# 8_-_DAC_and_MIC.net
KiCad netlist of a schematic drawn in Altium Designer
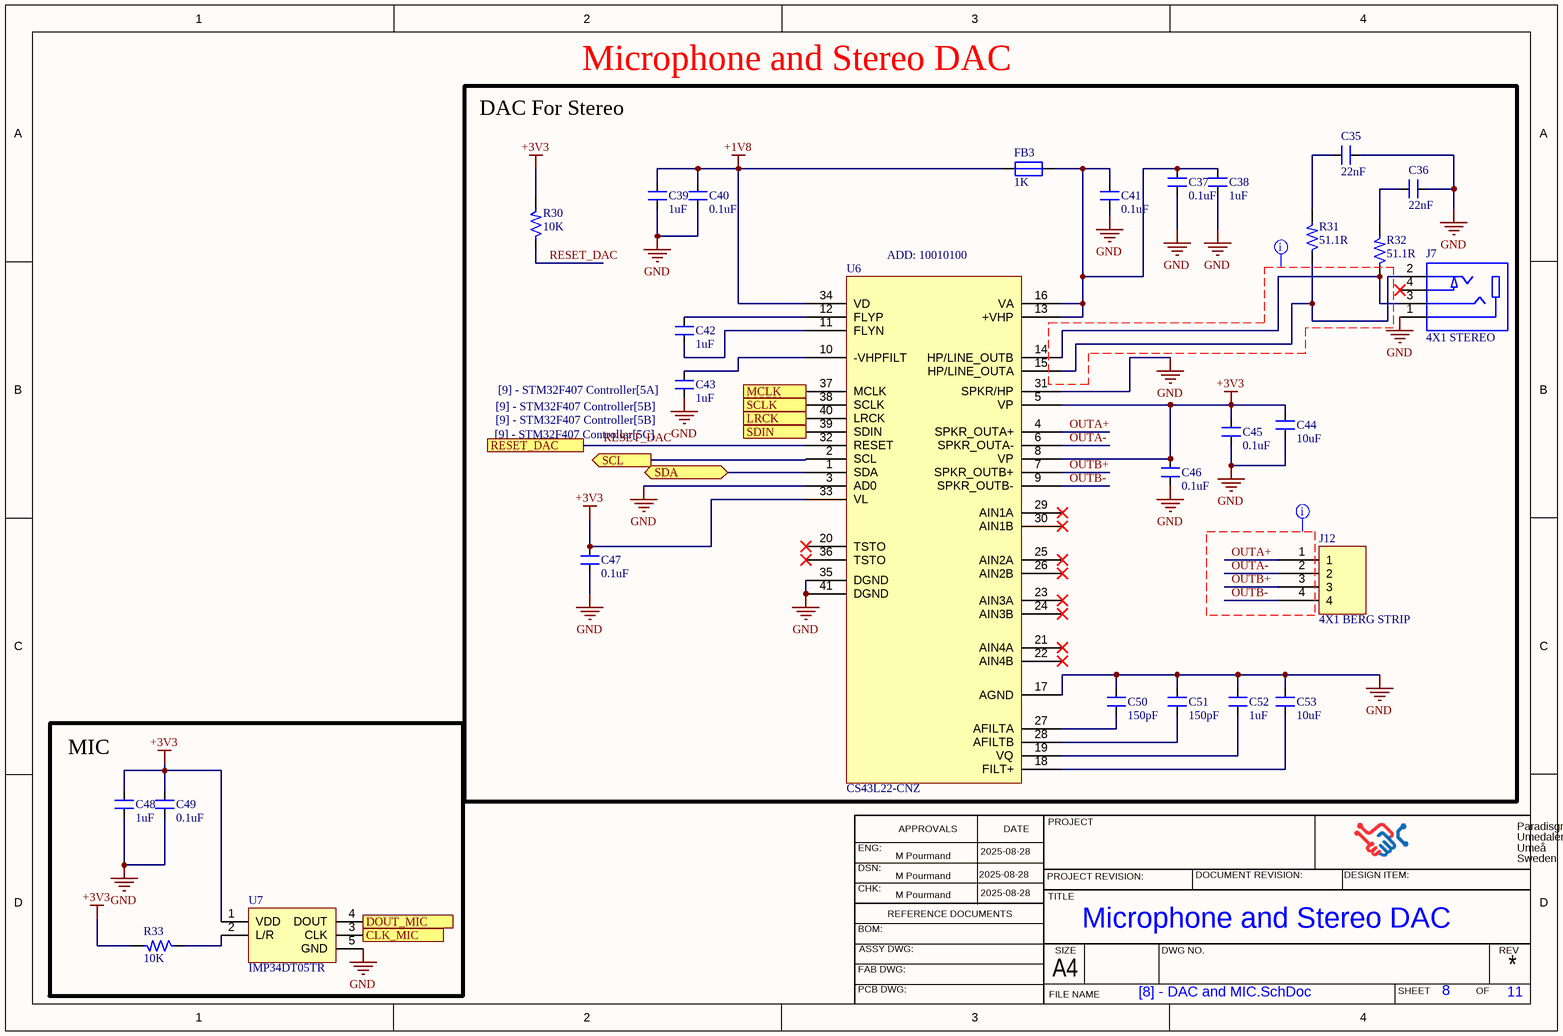
[diagram p0: [8] - DAC and MIC.SchDoc]

(export (version "E")
  (design (tool "Eeschema 10.0.6"))
  (components
    (comp (ref "C35")
      (value "22nF")
      (footprint "CAP_0805")
      (description "0.022µF ±10% 50V Ceramic Capacitor X7R 0805 (2012 Metric)")
      (fields
        (field (name "MANUFACTURER") "Samsung Electro-Mechanics")
        (field (name "MANUFACTURER PART NUMBER") "CL21B223KBANNNC")
      )
      (libsource (lib "ESTEEMPCBLIB") (part "CAP_22nF-50V-10%-0805"))
    )
    (comp (ref "C36")
      (value "22nF")
      (footprint "CAP_0805")
      (description "0.022µF ±10% 50V Ceramic Capacitor X7R 0805 (2012 Metric)")
      (fields
        (field (name "MANUFACTURER") "Samsung Electro-Mechanics")
        (field (name "MANUFACTURER PART NUMBER") "CL21B223KBANNNC")
      )
      (libsource (lib "ESTEEMPCBLIB") (part "CAP_22nF-50V-10%-0805"))
    )
    (comp (ref "C37")
      (value "0.1uF")
      (footprint "CAP_0805")
      (description "0.1µF ±5% 50V Ceramic Capacitor X7R 0805 (2012 Metric)")
      (fields
        (field (name "MANUFACTURER") "AVX Corporation")
        (field (name "MANUFACTURER PART NUMBER") "08055C104JAT4A")
      )
      (libsource (lib "ESTEEMPCBLIB") (part "CAP_0.1uF-50V-5%-0805"))
    )
    (comp (ref "C38")
      (value "1uF")
      (footprint "CAP_0805")
      (description "1µF ±5% 50V Ceramic Capacitor X7R 0805 (2012 Metric)")
      (fields
        (field (name "MANUFACTURER") "Samsung")
        (field (name "MANUFACTURER PART NUMBER") "CC0805JKX7R9BB105")
      )
      (libsource (lib "ESTEEMPCBLIB") (part "CAP_1uF-50V-5%-0805"))
    )
    (comp (ref "C39")
      (value "1uF")
      (footprint "CAP_0805")
      (description "1µF ±5% 50V Ceramic Capacitor X7R 0805 (2012 Metric)")
      (fields
        (field (name "MANUFACTURER") "Samsung")
        (field (name "MANUFACTURER PART NUMBER") "CC0805JKX7R9BB105")
      )
      (libsource (lib "ESTEEMPCBLIB") (part "CAP_1uF-50V-5%-0805"))
    )
    (comp (ref "C40")
      (value "0.1uF")
      (footprint "CAP_0805")
      (description "0.1µF ±5% 50V Ceramic Capacitor X7R 0805 (2012 Metric)")
      (fields
        (field (name "MANUFACTURER") "AVX Corporation")
        (field (name "MANUFACTURER PART NUMBER") "08055C104JAT4A")
      )
      (libsource (lib "ESTEEMPCBLIB") (part "CAP_0.1uF-50V-5%-0805"))
    )
    (comp (ref "C41")
      (value "0.1uF")
      (footprint "CAP_0805")
      (description "0.1µF ±5% 50V Ceramic Capacitor X7R 0805 (2012 Metric)")
      (fields
        (field (name "MANUFACTURER") "AVX Corporation")
        (field (name "MANUFACTURER PART NUMBER") "08055C104JAT4A")
      )
      (libsource (lib "ESTEEMPCBLIB") (part "CAP_0.1uF-50V-5%-0805"))
    )
    (comp (ref "C42")
      (value "1uF")
      (footprint "CAP_0805")
      (description "1µF ±5% 50V Ceramic Capacitor X7R 0805 (2012 Metric)")
      (fields
        (field (name "MANUFACTURER") "Samsung")
        (field (name "MANUFACTURER PART NUMBER") "CC0805JKX7R9BB105")
      )
      (libsource (lib "ESTEEMPCBLIB") (part "CAP_1uF-50V-5%-0805"))
    )
    (comp (ref "C43")
      (value "1uF")
      (footprint "CAP_0805")
      (description "1µF ±5% 50V Ceramic Capacitor X7R 0805 (2012 Metric)")
      (fields
        (field (name "MANUFACTURER") "Samsung")
        (field (name "MANUFACTURER PART NUMBER") "CC0805JKX7R9BB105")
      )
      (libsource (lib "ESTEEMPCBLIB") (part "CAP_1uF-50V-5%-0805"))
    )
    (comp (ref "C44")
      (value "10uF")
      (footprint "CAP_1206")
      (description "10µF ±10% 50V Ceramic Capacitor X7R 1206 (3216 Metric)")
      (fields
        (field (name "MANUFACTURER") "KEMET")
        (field (name "MANUFACTURER PART NUMBER") "CL31B106KBHNNNE")
      )
      (libsource (lib "ESTEEMPCBLIB") (part "CAP_10uF-50V-10%-1206"))
    )
    (comp (ref "C45")
      (value "0.1uF")
      (footprint "CAP_0805")
      (description "0.1µF ±5% 50V Ceramic Capacitor X7R 0805 (2012 Metric)")
      (fields
        (field (name "MANUFACTURER") "AVX Corporation")
        (field (name "MANUFACTURER PART NUMBER") "08055C104JAT4A")
      )
      (libsource (lib "ESTEEMPCBLIB") (part "CAP_0.1uF-50V-5%-0805"))
    )
    (comp (ref "C46")
      (value "0.1uF")
      (footprint "CAP_0805")
      (description "0.1µF ±5% 50V Ceramic Capacitor X7R 0805 (2012 Metric)")
      (fields
        (field (name "MANUFACTURER") "AVX Corporation")
        (field (name "MANUFACTURER PART NUMBER") "08055C104JAT4A")
      )
      (libsource (lib "ESTEEMPCBLIB") (part "CAP_0.1uF-50V-5%-0805"))
    )
    (comp (ref "C47")
      (value "0.1uF")
      (footprint "CAP_0805")
      (description "0.1µF ±5% 50V Ceramic Capacitor X7R 0805 (2012 Metric)")
      (fields
        (field (name "MANUFACTURER") "AVX Corporation")
        (field (name "MANUFACTURER PART NUMBER") "08055C104JAT4A")
      )
      (libsource (lib "ESTEEMPCBLIB") (part "CAP_0.1uF-50V-5%-0805"))
    )
    (comp (ref "C48")
      (value "1uF")
      (footprint "CAP_0805")
      (description "1µF ±5% 50V Ceramic Capacitor X7R 0805 (2012 Metric)")
      (fields
        (field (name "MANUFACTURER") "Samsung")
        (field (name "MANUFACTURER PART NUMBER") "CC0805JKX7R9BB105")
      )
      (libsource (lib "ESTEEMPCBLIB") (part "CAP_1uF-50V-5%-0805"))
    )
    (comp (ref "C49")
      (value "0.1uF")
      (footprint "CAP_0805")
      (description "0.1µF ±5% 50V Ceramic Capacitor X7R 0805 (2012 Metric)")
      (fields
        (field (name "MANUFACTURER") "AVX Corporation")
        (field (name "MANUFACTURER PART NUMBER") "08055C104JAT4A")
      )
      (libsource (lib "ESTEEMPCBLIB") (part "CAP_0.1uF-50V-5%-0805"))
    )
    (comp (ref "C50")
      (value "150pF")
      (footprint "CAP_0805")
      (description "150pF ±10% 50V Ceramic Capacitor C0G, NP0 0805 (2012 Metric)")
      (fields
        (field (name "MANUFACTURER") "AVX Corporation")
        (field (name "MANUFACTURER PART NUMBER") "08055A151KAT2A")
      )
      (libsource (lib "ESTEEMPCBLIB") (part "CAP_150pF-50V-10%-0805"))
    )
    (comp (ref "C51")
      (value "150pF")
      (footprint "CAP_0805")
      (description "150pF ±10% 50V Ceramic Capacitor C0G, NP0 0805 (2012 Metric)")
      (fields
        (field (name "MANUFACTURER") "AVX Corporation")
        (field (name "MANUFACTURER PART NUMBER") "08055A151KAT2A")
      )
      (libsource (lib "ESTEEMPCBLIB") (part "CAP_150pF-50V-10%-0805"))
    )
    (comp (ref "C52")
      (value "1uF")
      (footprint "CAP_0805")
      (description "1µF ±5% 50V Ceramic Capacitor X7R 0805 (2012 Metric)")
      (fields
        (field (name "MANUFACTURER") "Samsung")
        (field (name "MANUFACTURER PART NUMBER") "CC0805JKX7R9BB105")
      )
      (libsource (lib "ESTEEMPCBLIB") (part "CAP_1uF-50V-5%-0805"))
    )
    (comp (ref "C53")
      (value "10uF")
      (footprint "CAP_1206")
      (description "10µF ±10% 50V Ceramic Capacitor X7R 1206 (3216 Metric)")
      (fields
        (field (name "MANUFACTURER") "KEMET")
        (field (name "MANUFACTURER PART NUMBER") "CL31B106KBHNNNE")
      )
      (libsource (lib "ESTEEMPCBLIB") (part "CAP_10uF-50V-10%-1206"))
    )
    (comp (ref "FB3")
      (value "1K")
      (footprint "IND_0805")
      (description "1 kOhms @ 100MHz 1 Power Line Ferrite Bead 0805 (2012 Metric) 1.6A")
      (fields
        (field (name "MANUFACTURER") "Laird")
        (field (name "MANUFACTURER PART NUMBER") "BLM21SP102SH1D")
      )
      (libsource (lib "ESTEEMPCBLIB") (part "FB_1K-100MHZ-1.6A-0805"))
    )
    (comp (ref "J7")
      (value "4X1 STEREO")
      (footprint "CON_SJ-2504A-SMT-TR_SMD")
      (fields
        (field (name "MANUFACTURER") "CUI Devices")
        (field (name "MANUFACTURER PART NUMBER") "SJ-2504A-SMT-TR")
      )
      (libsource (lib "ESTEEMPCBLIB") (part "CON-PLG-STEREO_4X1-100-RA-SMD"))
    )
    (comp (ref "J12")
      (value "4X1 BERG STRIP")
      (footprint "CON4_100_40D72_TH_ST_MALE")
      (description "4 Pins, 1 Row 2.54mm Pitch, Straight bergstrip, Male")
      (fields (field (name "MANUFACTURER") "NA"))
      (libsource (lib "ESTEEMPCBLIB") (part "CON-BS-PLG_4X1-100-ST-TH"))
    )
    (comp (ref "R30")
      (value "10K")
      (footprint "RES_0603")
      (description "10 kOhms ±1% 0.1W, 1/10W Chip Resistor 0603 (1608 Metric) Automotive AEC-Q200 Thick Film")
      (fields (field (name "MANUFACTURER") "Walsin") (field (name "MANUFACTURER PART NUMBER") "WR06X1002FTL"))
      (libsource (lib "ESTEEMPCBLIB") (part "RES_10K-0.1W-1%-0603"))
    )
    (comp (ref "R31")
      (value "51.1R")
      (footprint "RES_0603")
      (description "51.1 Ohms ±1% 0.1W, 1/10W Chip Resistor 0603 (1608 Metric) Thick Film")
      (fields
        (field (name "MANUFACTURER") "Vishay Dale")
        (field (name "MANUFACTURER PART NUMBER") "CRCW060351R1FKEAC")
      )
      (libsource (lib "ESTEEMPCBLIB") (part "RES_51.1R-0.1W-1%-0603"))
    )
    (comp (ref "R32")
      (value "51.1R")
      (footprint "RES_0603")
      (description "51.1 Ohms ±1% 0.1W, 1/10W Chip Resistor 0603 (1608 Metric) Thick Film")
      (fields
        (field (name "MANUFACTURER") "Vishay Dale")
        (field (name "MANUFACTURER PART NUMBER") "CRCW060351R1FKEAC")
      )
      (libsource (lib "ESTEEMPCBLIB") (part "RES_51.1R-0.1W-1%-0603"))
    )
    (comp (ref "R33")
      (value "10K")
      (footprint "RES_0603")
      (description "10 kOhms ±1% 0.1W, 1/10W Chip Resistor 0603 (1608 Metric) Automotive AEC-Q200 Thick Film")
      (fields (field (name "MANUFACTURER") "Walsin") (field (name "MANUFACTURER PART NUMBER") "WR06X1002FTL"))
      (libsource (lib "ESTEEMPCBLIB") (part "RES_10K-0.1W-1%-0603"))
    )
    (comp (ref "U6")
      (value "CS43L22-CNZ")
      (footprint "QFN40_19_284_33X9_SMD")
      (description "Audio D/A Converter ICs Low Power Stereo DAC w/ClassD Spkr Driver")
      (fields (field (name "MANUFACTURER") "Cirrus Logic"))
      (libsource (lib "ESTEEMPCBLIB") (part "IC_CS43L22"))
    )
    (comp (ref "U7")
      (value "IMP34DT05TR")
      (footprint "HCLGA-4_53_137_15X37_SMD")
      (description "MEMS Microphones AUTO & INDUSTRIAL SENSORS")
      (fields (field (name "MANUFACTURER") "STMicroelectronics"))
      (libsource (lib "ESTEEMPCBLIB") (part "IC_IMP34DT05TR"))
    )
  )
  (nets
    (net (code "1") (name "+1V8") (class "Default")
      (node (ref "C39") (pin "2") (pinfunction "2_2") (pintype "passive"))
      (node (ref "C40") (pin "2") (pinfunction "2_2") (pintype "passive"))
      (node (ref "FB3") (pin "1") (pinfunction "1_1") (pintype "passive"))
      (node (ref "U6") (pin "34") (pinfunction "VD_34") (pintype "passive"))
    )
    (net (code "2") (name "+3V3") (class "Default")
      (node (ref "C44") (pin "1") (pinfunction "1_1") (pintype "passive"))
      (node (ref "C45") (pin "2") (pinfunction "2_2") (pintype "passive"))
      (node (ref "C46") (pin "2") (pinfunction "2_2") (pintype "passive"))
      (node (ref "C47") (pin "2") (pinfunction "2_2") (pintype "passive"))
      (node (ref "C48") (pin "2") (pinfunction "2_2") (pintype "passive"))
      (node (ref "C49") (pin "2") (pinfunction "2_2") (pintype "passive"))
      (node (ref "R30") (pin "2") (pinfunction "2_2") (pintype "passive"))
      (node (ref "R33") (pin "2") (pinfunction "2_2") (pintype "passive"))
      (node (ref "U6") (pin "33") (pinfunction "VL_33") (pintype "passive"))
      (node (ref "U6") (pin "5") (pinfunction "VP_5") (pintype "passive"))
      (node (ref "U6") (pin "8") (pinfunction "VP_8") (pintype "passive"))
      (node (ref "U7") (pin "1") (pinfunction "VDD_1") (pintype "passive"))
    )
    (net (code "3") (name "/CLK_MIC") (class "Default")
      (node (ref "U7") (pin "3") (pinfunction "CLK_3") (pintype "passive"))
    )
    (net (code "4") (name "/DOUT_MIC") (class "Default")
      (node (ref "U7") (pin "4") (pinfunction "DOUT_4") (pintype "passive"))
    )
    (net (code "5") (name "/LRCK") (class "Default")
      (node (ref "U6") (pin "40") (pinfunction "LRCK_40") (pintype "passive"))
    )
    (net (code "6") (name "/MCLK") (class "Default")
      (node (ref "U6") (pin "37") (pinfunction "MCLK_37") (pintype "passive"))
    )
    (net (code "7") (name "/OUTA+") (class "Default")
      (node (ref "J12") (pin "1") (pinfunction "1_1") (pintype "passive"))
      (node (ref "U6") (pin "4") (pinfunction "SPKR_OUTA+_4") (pintype "passive"))
    )
    (net (code "8") (name "/OUTA-") (class "Default")
      (node (ref "J12") (pin "2") (pinfunction "2_2") (pintype "passive"))
      (node (ref "U6") (pin "6") (pinfunction "SPKR_OUTA-_6") (pintype "passive"))
    )
    (net (code "9") (name "/OUTB+") (class "Default")
      (node (ref "J12") (pin "3") (pinfunction "3_3") (pintype "passive"))
      (node (ref "U6") (pin "7") (pinfunction "SPKR_OUTB+_7") (pintype "passive"))
    )
    (net (code "10") (name "/OUTB-") (class "Default")
      (node (ref "J12") (pin "4") (pinfunction "4_4") (pintype "passive"))
      (node (ref "U6") (pin "9") (pinfunction "SPKR_OUTB-_9") (pintype "passive"))
    )
    (net (code "11") (name "/RESET_DAC") (class "Default")
      (node (ref "R30") (pin "1") (pinfunction "1_1") (pintype "passive"))
      (node (ref "U6") (pin "32") (pinfunction "RESET_32") (pintype "passive"))
    )
    (net (code "12") (name "/SCL") (class "Default")
      (node (ref "U6") (pin "2") (pinfunction "SCL_2") (pintype "passive"))
    )
    (net (code "13") (name "/SCLK") (class "Default")
      (node (ref "U6") (pin "38") (pinfunction "SCLK_38") (pintype "passive"))
    )
    (net (code "14") (name "/SDA") (class "Default")
      (node (ref "U6") (pin "1") (pinfunction "SDA_1") (pintype "passive"))
    )
    (net (code "15") (name "/SDIN") (class "Default")
      (node (ref "U6") (pin "39") (pinfunction "SDIN_39") (pintype "passive"))
    )
    (net (code "16") (name "GND") (class "Default")
      (node (ref "C35") (pin "2") (pinfunction "2_2") (pintype "passive"))
      (node (ref "C36") (pin "2") (pinfunction "2_2") (pintype "passive"))
      (node (ref "C37") (pin "1") (pinfunction "1_1") (pintype "passive"))
      (node (ref "C38") (pin "1") (pinfunction "1_1") (pintype "passive"))
      (node (ref "C39") (pin "1") (pinfunction "1_1") (pintype "passive"))
      (node (ref "C40") (pin "1") (pinfunction "1_1") (pintype "passive"))
      (node (ref "C41") (pin "1") (pinfunction "1_1") (pintype "passive"))
      (node (ref "C43") (pin "1") (pinfunction "1_1") (pintype "passive"))
      (node (ref "C44") (pin "2") (pinfunction "2_2") (pintype "passive"))
      (node (ref "C45") (pin "1") (pinfunction "1_1") (pintype "passive"))
      (node (ref "C46") (pin "1") (pinfunction "1_1") (pintype "passive"))
      (node (ref "C47") (pin "1") (pinfunction "1_1") (pintype "passive"))
      (node (ref "C48") (pin "1") (pinfunction "1_1") (pintype "passive"))
      (node (ref "C49") (pin "1") (pinfunction "1_1") (pintype "passive"))
      (node (ref "C50") (pin "2") (pinfunction "2_2") (pintype "passive"))
      (node (ref "C51") (pin "2") (pinfunction "2_2") (pintype "passive"))
      (node (ref "C52") (pin "2") (pinfunction "2_2") (pintype "passive"))
      (node (ref "C53") (pin "1") (pinfunction "1_1") (pintype "passive"))
      (node (ref "J7") (pin "1") (pinfunction "1_1") (pintype "passive"))
      (node (ref "U6") (pin "17") (pinfunction "AGND_17") (pintype "passive"))
      (node (ref "U6") (pin "3") (pinfunction "AD0_3") (pintype "passive"))
      (node (ref "U6") (pin "31") (pinfunction "SPKR/HP_31") (pintype "passive"))
      (node (ref "U6") (pin "35") (pinfunction "DGND_35") (pintype "passive"))
      (node (ref "U6") (pin "41") (pinfunction "DGND_41") (pintype "passive"))
      (node (ref "U7") (pin "5") (pinfunction "GND_5") (pintype "passive"))
    )
    (net (code "17") (name "Net-(C35-Pad1)") (class "Default")
      (node (ref "C35") (pin "1") (pinfunction "1_1") (pintype "passive"))
      (node (ref "R31") (pin "2") (pinfunction "2_2") (pintype "passive"))
    )
    (net (code "18") (name "Net-(C36-Pad1)") (class "Default")
      (node (ref "C36") (pin "1") (pinfunction "1_1") (pintype "passive"))
      (node (ref "R32") (pin "2") (pinfunction "2_2") (pintype "passive"))
    )
    (net (code "19") (name "Net-(U6-+VHP)") (class "Default")
      (node (ref "C37") (pin "2") (pinfunction "2_2") (pintype "passive"))
      (node (ref "C38") (pin "2") (pinfunction "2_2") (pintype "passive"))
      (node (ref "C41") (pin "2") (pinfunction "2_2") (pintype "passive"))
      (node (ref "FB3") (pin "2") (pinfunction "2_2") (pintype "passive"))
      (node (ref "U6") (pin "13") (pinfunction "+VHP_13") (pintype "passive"))
      (node (ref "U6") (pin "16") (pinfunction "VA_16") (pintype "passive"))
    )
    (net (code "20") (name "Net-(U6--VHPFILT)") (class "Default")
      (node (ref "C43") (pin "2") (pinfunction "2_2") (pintype "passive"))
      (node (ref "U6") (pin "10") (pinfunction "-VHPFILT_10") (pintype "passive"))
    )
    (net (code "21") (name "Net-(U6-AFILTA)") (class "Default")
      (node (ref "C50") (pin "1") (pinfunction "1_1") (pintype "passive"))
      (node (ref "U6") (pin "27") (pinfunction "AFILTA_27") (pintype "passive"))
    )
    (net (code "22") (name "Net-(U6-AFILTB)") (class "Default")
      (node (ref "C51") (pin "1") (pinfunction "1_1") (pintype "passive"))
      (node (ref "U6") (pin "28") (pinfunction "AFILTB_28") (pintype "passive"))
    )
    (net (code "23") (name "Net-(U6-FILT+)") (class "Default")
      (node (ref "C53") (pin "2") (pinfunction "2_2") (pintype "passive"))
      (node (ref "U6") (pin "18") (pinfunction "FILT+_18") (pintype "passive"))
    )
    (net (code "24") (name "Net-(U6-FLYN)") (class "Default")
      (node (ref "C42") (pin "1") (pinfunction "1_1") (pintype "passive"))
      (node (ref "U6") (pin "11") (pinfunction "FLYN_11") (pintype "passive"))
    )
    (net (code "25") (name "Net-(U6-FLYP)") (class "Default")
      (node (ref "C42") (pin "2") (pinfunction "2_2") (pintype "passive"))
      (node (ref "U6") (pin "12") (pinfunction "FLYP_12") (pintype "passive"))
    )
    (net (code "26") (name "Net-(U6-HP{slash}LINE_OUTA)") (class "Default")
      (node (ref "J7") (pin "2") (pinfunction "2_2") (pintype "passive"))
      (node (ref "R31") (pin "1") (pinfunction "1_1") (pintype "passive"))
      (node (ref "U6") (pin "15") (pinfunction "HP/LINE_OUTA_15") (pintype "passive"))
    )
    (net (code "27") (name "Net-(U6-HP{slash}LINE_OUTB)") (class "Default")
      (node (ref "J7") (pin "3") (pinfunction "3_3") (pintype "passive"))
      (node (ref "R32") (pin "1") (pinfunction "1_1") (pintype "passive"))
      (node (ref "U6") (pin "14") (pinfunction "HP/LINE_OUTB_14") (pintype "passive"))
    )
    (net (code "28") (name "Net-(U6-VQ)") (class "Default")
      (node (ref "C52") (pin "1") (pinfunction "1_1") (pintype "passive"))
      (node (ref "U6") (pin "19") (pinfunction "VQ_19") (pintype "passive"))
    )
    (net (code "29") (name "Net-(U7-L{slash}R)") (class "Default")
      (node (ref "R33") (pin "1") (pinfunction "1_1") (pintype "passive"))
      (node (ref "U7") (pin "2") (pinfunction "L/R_2") (pintype "passive"))
    )
    (net (code "30") (name "unconnected-(J7-Pad4)") (class "Default")
      (node (ref "J7") (pin "4") (pinfunction "4_4") (pintype "passive+no_connect"))
    )
    (net (code "31") (name "unconnected-(U6-AIN1A-Pad29)") (class "Default")
      (node (ref "U6") (pin "29") (pinfunction "AIN1A_29") (pintype "passive+no_connect"))
    )
    (net (code "32") (name "unconnected-(U6-AIN1B-Pad30)") (class "Default")
      (node (ref "U6") (pin "30") (pinfunction "AIN1B_30") (pintype "passive+no_connect"))
    )
    (net (code "33") (name "unconnected-(U6-AIN2A-Pad25)") (class "Default")
      (node (ref "U6") (pin "25") (pinfunction "AIN2A_25") (pintype "passive+no_connect"))
    )
    (net (code "34") (name "unconnected-(U6-AIN2B-Pad26)") (class "Default")
      (node (ref "U6") (pin "26") (pinfunction "AIN2B_26") (pintype "passive+no_connect"))
    )
    (net (code "35") (name "unconnected-(U6-AIN3A-Pad23)") (class "Default")
      (node (ref "U6") (pin "23") (pinfunction "AIN3A_23") (pintype "passive+no_connect"))
    )
    (net (code "36") (name "unconnected-(U6-AIN3B-Pad24)") (class "Default")
      (node (ref "U6") (pin "24") (pinfunction "AIN3B_24") (pintype "passive+no_connect"))
    )
    (net (code "37") (name "unconnected-(U6-AIN4A-Pad21)") (class "Default")
      (node (ref "U6") (pin "21") (pinfunction "AIN4A_21") (pintype "passive+no_connect"))
    )
    (net (code "38") (name "unconnected-(U6-AIN4B-Pad22)") (class "Default")
      (node (ref "U6") (pin "22") (pinfunction "AIN4B_22") (pintype "passive+no_connect"))
    )
    (net (code "39") (name "unconnected-(U6-TSTO-Pad20)") (class "Default")
      (node (ref "U6") (pin "20") (pinfunction "TSTO_20") (pintype "passive+no_connect"))
    )
    (net (code "40") (name "unconnected-(U6-TSTO-Pad36)") (class "Default")
      (node (ref "U6") (pin "36") (pinfunction "TSTO_36") (pintype "passive+no_connect"))
    )
  )
)
